# LiDAR_Lite_Interface_HardSwitch.net
KiCad netlist of a schematic drawn in EAGLE
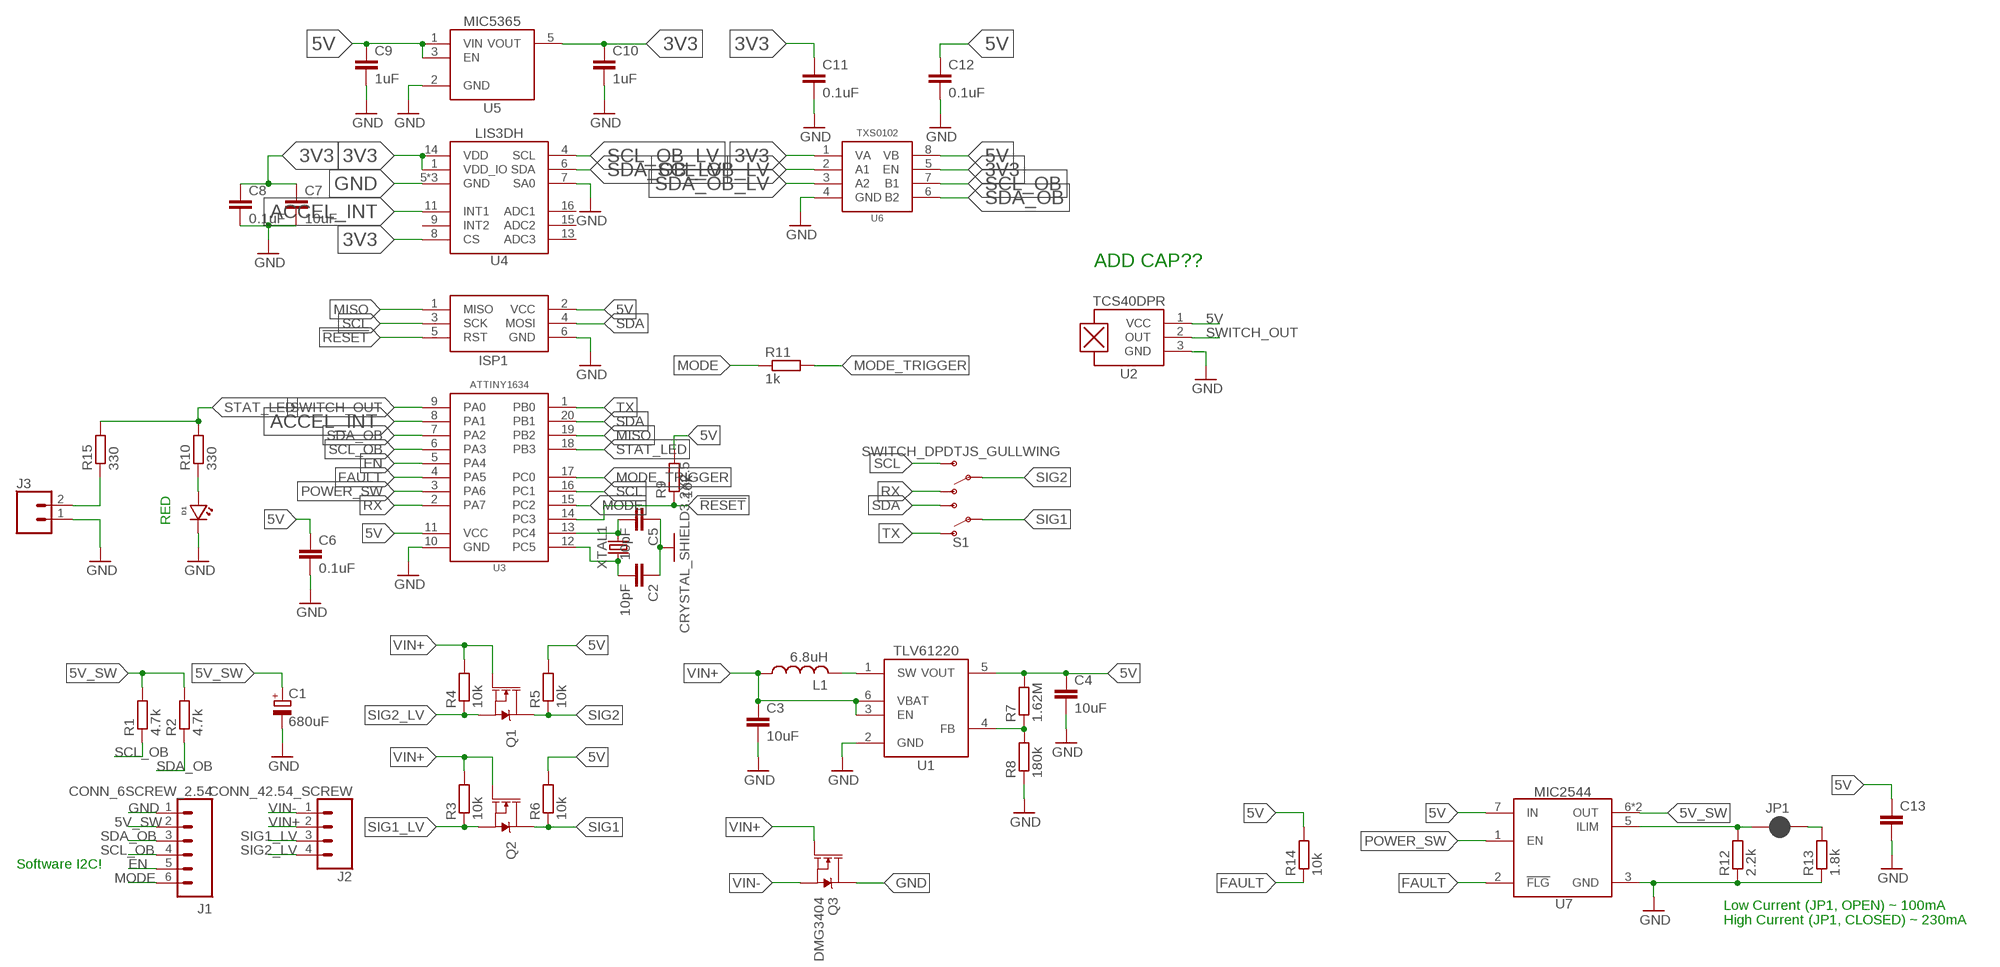
[diagram p0: schematic, sheet 1]

(export (version "E")
  (design (tool "Eeschema 10.0.6"))
  (components
    (comp (ref "C1")
      (value "680uF")
      (footprint "eagle-import:UW-10X10_NICHICON")
      (fields (field (name "MF") "Nichicon") (field (name "MPN") "UWT1C681MNL1GS"))
      (libsource (lib "eagle-import") (part "CPOL-EUUW-10X10"))
    )
    (comp (ref "C2")
      (value "10pF")
      (footprint "eagle-import:C0603")
      (fields (field (name "MF") "Yageo") (field (name "MPN") "CC0603JRNPO9BN100CC0603JRNPO9BN100"))
      (libsource (lib "eagle-import") (part "C-EUC060310PF"))
    )
    (comp (ref "C3")
      (value "10uF")
      (footprint "eagle-import:C0805")
      (fields (field (name "MF") "Murata") (field (name "MPN") "GRM21BR61C106KE15K"))
      (libsource (lib "eagle-import") (part "C-EUC080510UF"))
    )
    (comp (ref "C4")
      (value "10uF")
      (footprint "eagle-import:C0805")
      (fields (field (name "MF") "Murata") (field (name "MPN") "GRM21BR61C106KE15K"))
      (libsource (lib "eagle-import") (part "C-EUC080510UF"))
    )
    (comp (ref "C5")
      (value "10pF")
      (footprint "eagle-import:C0603")
      (fields (field (name "MF") "Yageo") (field (name "MPN") "CC0603JRNPO9BN100CC0603JRNPO9BN100"))
      (libsource (lib "eagle-import") (part "C-EUC060310PF"))
    )
    (comp (ref "C6")
      (value "0.1uF")
      (footprint "eagle-import:C0603")
      (fields (field (name "MF") "Murata") (field (name "MPN") "GCM188R71E104KA57D"))
      (libsource (lib "eagle-import") (part "C-EUC06030.1UF"))
    )
    (comp (ref "C7")
      (value "10uF")
      (footprint "eagle-import:C0805")
      (fields (field (name "MF") "Murata") (field (name "MPN") "GRM21BR61C106KE15K"))
      (libsource (lib "eagle-import") (part "C-EUC080510UF"))
    )
    (comp (ref "C8")
      (value "0.1uF")
      (footprint "eagle-import:C0603")
      (fields (field (name "MF") "Murata") (field (name "MPN") "GCM188R71E104KA57D"))
      (libsource (lib "eagle-import") (part "C-EUC06030.1UF"))
    )
    (comp (ref "C9")
      (value "1uF")
      (footprint "eagle-import:C0603")
      (fields (field (name "MF") "Murata") (field (name "MPN") "GRM188R61C105KA12D"))
      (libsource (lib "eagle-import") (part "C-EUC06031UF"))
    )
    (comp (ref "C10")
      (value "1uF")
      (footprint "eagle-import:C0603")
      (fields (field (name "MF") "Murata") (field (name "MPN") "GRM188R61C105KA12D"))
      (libsource (lib "eagle-import") (part "C-EUC06031UF"))
    )
    (comp (ref "C11")
      (value "0.1uF")
      (footprint "eagle-import:C0402")
      (fields (field (name "MF") "Murata") (field (name "MPN") "GCM155R71C104KA55D"))
      (libsource (lib "eagle-import") (part "C-EUC04020.1UF"))
    )
    (comp (ref "C12")
      (value "0.1uF")
      (footprint "eagle-import:C0402")
      (fields (field (name "MF") "Murata") (field (name "MPN") "GCM155R71C104KA55D"))
      (libsource (lib "eagle-import") (part "C-EUC04020.1UF"))
    )
    (comp (ref "C13")
      (value "C-EU0.1UFC0603")
      (footprint "eagle-import:C0603")
      (fields (field (name "MF") "Murata") (field (name "MPN") "GCM188R71E104KA57D"))
      (libsource (lib "eagle-import") (part "C-EUC06030.1UF"))
    )
    (comp (ref "D1")
      (value "LED0603")
      (footprint "eagle-import:LED_0603")
      (fields
        (field (name "DIGIKEY") "732-4978-1-ND")
        (field (name "MF") "Wurth")
        (field (name "MPN") "150060RS75000")
      )
      (libsource (lib "eagle-import") (part "LED0603"))
    )
    (comp (ref "ISP1")
      (value "AVRISP-6")
      (footprint "eagle-import:AVRISP")
      (libsource (lib "eagle-import") (part "AVRISP-6"))
    )
    (comp (ref "J1")
      (value "CONN_6SCREW_2.54")
      (footprint "eagle-import:1X06_SCREW")
      (fields (field (name "MF") "OnShore") (field (name "MPN") "OSTVN06A150"))
      (libsource (lib "eagle-import") (part "CONN_6SCREW_2.54"))
    )
    (comp (ref "J2")
      (value "CONN_42.54_SCREW")
      (footprint "eagle-import:1X04_SCREW")
      (fields (field (name "MF") "On Shore") (field (name "MPN") "OSTVN04A150"))
      (libsource (lib "eagle-import") (part "CONN_42.54_SCREW"))
    )
    (comp (ref "J3")
      (value "CONN_02")
      (footprint "eagle-import:1X02")
      (libsource (lib "eagle-import") (part "CONN_02"))
    )
    (comp (ref "JP1")
      (value "JUMPER-SMT_2_NC_PASTE_SILK")
      (footprint "eagle-import:SMT-JUMPER_2_NC_PASTE_SILK")
      (libsource (lib "eagle-import") (part "JUMPER-SMT_2_NC_PASTE_SILK"))
    )
    (comp (ref "L1")
      (value "6.8uH")
      (footprint "eagle-import:1008")
      (fields (field (name "MF") "Wurth") (field (name "MPN") "74438323068"))
      (libsource (lib "eagle-import") (part "INDUCTOR1008"))
    )
    (comp (ref "Q1")
      (value "MOSFET-NCH-2N7002P")
      (footprint "eagle-import:SOT23-3")
      (fields (field (name "MF") "Nexperia") (field (name "MPN") "2N7002P,215"))
      (libsource (lib "eagle-import") (part "MOSFET-NCH-2N7002P"))
    )
    (comp (ref "Q2")
      (value "MOSFET-NCH-2N7002P")
      (footprint "eagle-import:SOT23-3")
      (fields (field (name "MF") "Nexperia") (field (name "MPN") "2N7002P,215"))
      (libsource (lib "eagle-import") (part "MOSFET-NCH-2N7002P"))
    )
    (comp (ref "Q3")
      (value "DMG3404")
      (footprint "eagle-import:SOT23-3")
      (fields (field (name "MF") "Diodes Incorporated") (field (name "MPN") "DMG3404L-7"))
      (libsource (lib "eagle-import") (part "MOSFET-NCH-DMG3404L"))
    )
    (comp (ref "R1")
      (value "4.7k")
      (footprint "eagle-import:R0603")
      (fields (field (name "MF") "Yageo") (field (name "MPN") "RC0603FR-074K7L"))
      (libsource (lib "eagle-import") (part "R-EU_R06034.7K"))
    )
    (comp (ref "R2")
      (value "4.7k")
      (footprint "eagle-import:R0603")
      (fields (field (name "MF") "Yageo") (field (name "MPN") "RC0603FR-074K7L"))
      (libsource (lib "eagle-import") (part "R-EU_R06034.7K"))
    )
    (comp (ref "R3")
      (value "10k")
      (footprint "eagle-import:R0603")
      (fields (field (name "MF") "Yageo") (field (name "MPN") "RC0603FR-0710KL"))
      (libsource (lib "eagle-import") (part "R-EU_R060310K"))
    )
    (comp (ref "R4")
      (value "10k")
      (footprint "eagle-import:R0603")
      (fields (field (name "MF") "Yageo") (field (name "MPN") "RC0603FR-0710KL"))
      (libsource (lib "eagle-import") (part "R-EU_R060310K"))
    )
    (comp (ref "R5")
      (value "10k")
      (footprint "eagle-import:R0603")
      (fields (field (name "MF") "Yageo") (field (name "MPN") "RC0603FR-0710KL"))
      (libsource (lib "eagle-import") (part "R-EU_R060310K"))
    )
    (comp (ref "R6")
      (value "10k")
      (footprint "eagle-import:R0603")
      (fields (field (name "MF") "Yageo") (field (name "MPN") "RC0603FR-0710KL"))
      (libsource (lib "eagle-import") (part "R-EU_R060310K"))
    )
    (comp (ref "R7")
      (value "1.62M")
      (footprint "eagle-import:R0603")
      (fields (field (name "MF") "Stackpole") (field (name "MPN") "RMCF0603FT1M62"))
      (libsource (lib "eagle-import") (part "R-EU_R06031.62M"))
    )
    (comp (ref "R8")
      (value "180k")
      (footprint "eagle-import:R0603")
      (fields (field (name "MF") "Panasonic") (field (name "MPN") "ERJ-3EKF1803V"))
      (libsource (lib "eagle-import") (part "R-EU_R0603180K"))
    )
    (comp (ref "R9")
      (value "10k")
      (footprint "eagle-import:R0603")
      (fields (field (name "MF") "Yageo") (field (name "MPN") "RC0603FR-0710KL"))
      (libsource (lib "eagle-import") (part "R-EU_R060310K"))
    )
    (comp (ref "R10")
      (value "330")
      (footprint "eagle-import:R0603")
      (fields (field (name "MF") "Yageo") (field (name "MPN") "RC0603FR-07330RL"))
      (libsource (lib "eagle-import") (part "R-EU_R0603330"))
    )
    (comp (ref "R11")
      (value "1k")
      (footprint "eagle-import:R0603")
      (fields (field (name "MF") "Yageo") (field (name "MPN") "AC0603FR-071KL"))
      (libsource (lib "eagle-import") (part "R-EU_R06031K"))
    )
    (comp (ref "R12")
      (value "2.2k")
      (footprint "eagle-import:R0603")
      (fields (field (name "MF") "Yageo") (field (name "MPN") "RC0603FR-072K2L"))
      (libsource (lib "eagle-import") (part "R-EU_R06032.2K"))
    )
    (comp (ref "R13")
      (value "1.8k")
      (footprint "eagle-import:R0603")
      (fields (field (name "MF") "Yageo") (field (name "MPN") "RC0603FR-071K8L"))
      (libsource (lib "eagle-import") (part "R-EU_R06031.8K"))
    )
    (comp (ref "R14")
      (value "10k")
      (footprint "eagle-import:R0603")
      (fields (field (name "MF") "Yageo") (field (name "MPN") "RC0603FR-0710KL"))
      (libsource (lib "eagle-import") (part "R-EU_R060310K"))
    )
    (comp (ref "R15")
      (value "330")
      (footprint "eagle-import:R0603")
      (fields (field (name "MF") "Yageo") (field (name "MPN") "RC0603FR-07330RL"))
      (libsource (lib "eagle-import") (part "R-EU_R0603330"))
    )
    (comp (ref "S1")
      (value "SWITCH_DPDTJS_GULLWING")
      (footprint "eagle-import:JS202011SCQN")
      (fields (field (name "MF") "C&K") (field (name "MPN") "JS202011SCQN"))
      (libsource (lib "eagle-import") (part "SWITCH_DPDTJS_GULLWING"))
    )
    (comp (ref "U1")
      (value "TLV61220DBV")
      (footprint "eagle-import:DBV_R-PDSO-G6")
      (fields (field (name "MF") "TI") (field (name "MPN") "TLV61220DBVR"))
      (libsource (lib "eagle-import") (part "TLV61220DBV"))
    )
    (comp (ref "U2")
      (value "TCS40DPRSOT23")
      (footprint "eagle-import:SOT23-3")
      (fields
        (field (name "DISP") "TCS40DPR")
        (field (name "MF") "Toshiba")
        (field (name "MPN") "TCS40DPR,LF")
      )
      (libsource (lib "eagle-import") (part "TCS40DPRSOT23"))
    )
    (comp (ref "U3")
      (value "ATTINY1634SOIC")
      (footprint "eagle-import:SO-20DW")
      (fields (field (name "MF") "Atmel") (field (name "MPN") "ATTINY1634-SUR"))
      (libsource (lib "eagle-import") (part "ATTINY1634SOIC"))
    )
    (comp (ref "U4")
      (value "LIS3DHLGA")
      (footprint "eagle-import:LGA-16")
      (fields (field (name "MF") "ST") (field (name "MPN") "LIS3DHTR"))
      (libsource (lib "eagle-import") (part "LIS3DHLGA"))
    )
    (comp (ref "U5")
      (value "MIC53653.3SC70")
      (footprint "eagle-import:DCK_R-PDSO-G5")
      (fields (field (name "MF") "Microchip") (field (name "MPN") "MIC5365-3.3YC5-TR"))
      (libsource (lib "eagle-import") (part "MIC5365SC703.3"))
    )
    (comp (ref "U6")
      (value "TXS0102DQM")
      (footprint "eagle-import:DQM_R-PX2SON-N8")
      (fields (field (name "MF") "TI") (field (name "MPN") "TXS0102DQMR"))
      (libsource (lib "eagle-import") (part "TXS0102DQM"))
    )
    (comp (ref "U7")
      (value "MIC2544MSOP")
      (footprint "eagle-import:MSOP_8")
      (fields (field (name "MF") "Microchip") (field (name "MPN") "MIC2544-1YMM"))
      (libsource (lib "eagle-import") (part "MIC2544MSOP"))
    )
    (comp (ref "XTAL1")
      (value "CRYSTAL_SHIELD3.2X2.5")
      (footprint "eagle-import:CRYSTAL_3.2X2.5_4-SMD")
      (fields (field (name "MF") "Abricon") (field (name "MPN") "ABM8G-12.000MHZ-4Y-T3"))
      (libsource (lib "eagle-import") (part "CRYSTAL_SHIELD3.2X2.5"))
    )
  )
  (nets
    (net (code "1") (name "/~{RESET}") (class "Default")
      (node (ref "ISP1") (pin "5") (pinfunction "RST_5") (pintype "output"))
      (node (ref "R9") (pin "1") (pinfunction "1_1") (pintype "passive"))
      (node (ref "U3") (pin "14") (pinfunction "PC3_14") (pintype "bidirectional"))
    )
    (net (code "2") (name "3V3") (class "Default")
      (node (ref "C10") (pin "1") (pinfunction "1_1") (pintype "passive"))
      (node (ref "C11") (pin "1") (pinfunction "1_1") (pintype "passive"))
      (node (ref "C7") (pin "1") (pinfunction "1_1") (pintype "passive"))
      (node (ref "C8") (pin "1") (pinfunction "1_1") (pintype "passive"))
      (node (ref "U4") (pin "1") (pinfunction "VDD_IO_1") (pintype "bidirectional"))
      (node (ref "U4") (pin "14") (pinfunction "VDD_14") (pintype "bidirectional"))
      (node (ref "U4") (pin "8") (pinfunction "CS_8") (pintype "bidirectional"))
      (node (ref "U5") (pin "5") (pinfunction "VOUT_5") (pintype "power_in"))
      (node (ref "U6") (pin "1") (pinfunction "VA_1") (pintype "power_in"))
      (node (ref "U6") (pin "5") (pinfunction "EN_5") (pintype "input"))
    )
    (net (code "3") (name "5V") (class "Default")
      (node (ref "C12") (pin "1") (pinfunction "1_1") (pintype "passive"))
      (node (ref "C13") (pin "1") (pinfunction "1_1") (pintype "passive"))
      (node (ref "C4") (pin "1") (pinfunction "1_1") (pintype "passive"))
      (node (ref "C6") (pin "1") (pinfunction "1_1") (pintype "passive"))
      (node (ref "C9") (pin "1") (pinfunction "1_1") (pintype "passive"))
      (node (ref "ISP1") (pin "2") (pinfunction "VCC_2") (pintype "power_in"))
      (node (ref "R14") (pin "2") (pinfunction "2_2") (pintype "passive"))
      (node (ref "R5") (pin "2") (pinfunction "2_2") (pintype "passive"))
      (node (ref "R6") (pin "2") (pinfunction "2_2") (pintype "passive"))
      (node (ref "R7") (pin "2") (pinfunction "2_2") (pintype "passive"))
      (node (ref "R9") (pin "2") (pinfunction "2_2") (pintype "passive"))
      (node (ref "U1") (pin "5") (pinfunction "VOUT_5") (pintype "power_in"))
      (node (ref "U2") (pin "1") (pinfunction "VCC_1") (pintype "power_in"))
      (node (ref "U3") (pin "11") (pinfunction "VCC_11") (pintype "power_in"))
      (node (ref "U5") (pin "1") (pinfunction "VIN_1") (pintype "power_in"))
      (node (ref "U5") (pin "3") (pinfunction "EN_3") (pintype "input"))
      (node (ref "U6") (pin "8") (pinfunction "VB_8") (pintype "power_in"))
      (node (ref "U7") (pin "7") (pinfunction "IN_7") (pintype "power_in"))
    )
    (net (code "4") (name "5V_SW") (class "Default")
      (node (ref "C1") (pin "+") (pinfunction "+_+") (pintype "passive"))
      (node (ref "J1") (pin "2") (pinfunction "2_2") (pintype "passive"))
      (node (ref "R1") (pin "2") (pinfunction "2_2") (pintype "passive"))
      (node (ref "R2") (pin "2") (pinfunction "2_2") (pintype "passive"))
      (node (ref "U7") (pin "6") (pinfunction "OUT_6") (pintype "power_in"))
      (node (ref "U7") (pin "8") (pinfunction "OUT_8") (pintype "power_in"))
    )
    (net (code "5") (name "ACCEL_INT") (class "Default")
      (node (ref "U3") (pin "8") (pinfunction "PA1_8") (pintype "bidirectional"))
      (node (ref "U4") (pin "11") (pinfunction "INT1_11") (pintype "bidirectional"))
    )
    (net (code "6") (name "EN") (class "Default")
      (node (ref "J1") (pin "5") (pinfunction "5_5") (pintype "passive"))
      (node (ref "U3") (pin "5") (pinfunction "PA4_5") (pintype "bidirectional"))
    )
    (net (code "7") (name "FAULT") (class "Default")
      (node (ref "R14") (pin "1") (pinfunction "1_1") (pintype "passive"))
      (node (ref "U3") (pin "4") (pinfunction "PA5_4") (pintype "bidirectional"))
      (node (ref "U7") (pin "2") (pinfunction "~{FLG}_2") (pintype "output"))
    )
    (net (code "8") (name "GND") (class "Default")
      (node (ref "C1") (pin "-") (pinfunction "-_-") (pintype "passive"))
      (node (ref "C10") (pin "2") (pinfunction "2_2") (pintype "passive"))
      (node (ref "C11") (pin "2") (pinfunction "2_2") (pintype "passive"))
      (node (ref "C12") (pin "2") (pinfunction "2_2") (pintype "passive"))
      (node (ref "C13") (pin "2") (pinfunction "2_2") (pintype "passive"))
      (node (ref "C2") (pin "1") (pinfunction "1_1") (pintype "passive"))
      (node (ref "C3") (pin "2") (pinfunction "2_2") (pintype "passive"))
      (node (ref "C4") (pin "2") (pinfunction "2_2") (pintype "passive"))
      (node (ref "C5") (pin "1") (pinfunction "1_1") (pintype "passive"))
      (node (ref "C6") (pin "2") (pinfunction "2_2") (pintype "passive"))
      (node (ref "C7") (pin "2") (pinfunction "2_2") (pintype "passive"))
      (node (ref "C8") (pin "2") (pinfunction "2_2") (pintype "passive"))
      (node (ref "C9") (pin "2") (pinfunction "2_2") (pintype "passive"))
      (node (ref "D1") (pin "CATHODE") (pinfunction "CATHODE_CATHODE") (pintype "power_in"))
      (node (ref "ISP1") (pin "6") (pinfunction "GND_6") (pintype "power_in"))
      (node (ref "J1") (pin "1") (pinfunction "1_1") (pintype "passive"))
      (node (ref "J3") (pin "1") (pinfunction "1_1") (pintype "passive"))
      (node (ref "Q3") (pin "3") (pinfunction "D_3") (pintype "bidirectional"))
      (node (ref "R12") (pin "1") (pinfunction "1_1") (pintype "passive"))
      (node (ref "R13") (pin "1") (pinfunction "1_1") (pintype "passive"))
      (node (ref "R8") (pin "1") (pinfunction "1_1") (pintype "passive"))
      (node (ref "U1") (pin "2") (pinfunction "GND_2") (pintype "power_in"))
      (node (ref "U2") (pin "3") (pinfunction "GND_3") (pintype "power_in"))
      (node (ref "U3") (pin "10") (pinfunction "GND_10") (pintype "power_in"))
      (node (ref "U4") (pin "10") (pinfunction "GND_10") (pintype "bidirectional"))
      (node (ref "U4") (pin "12") (pinfunction "GND_12") (pintype "bidirectional"))
      (node (ref "U4") (pin "5") (pinfunction "GND_5") (pintype "bidirectional"))
      (node (ref "U4") (pin "7") (pinfunction "SA0_7") (pintype "bidirectional"))
      (node (ref "U5") (pin "2") (pinfunction "GND_2") (pintype "power_in"))
      (node (ref "U6") (pin "4") (pinfunction "GND_4") (pintype "power_in"))
      (node (ref "U7") (pin "3") (pinfunction "GND_3") (pintype "power_in"))
      (node (ref "XTAL1") (pin "2") (pinfunction "GND_2") (pintype "power_in"))
      (node (ref "XTAL1") (pin "4") (pinfunction "GND_4") (pintype "power_in"))
    )
    (net (code "9") (name "MISO") (class "Default")
      (node (ref "ISP1") (pin "1") (pinfunction "MISO_1") (pintype "input"))
      (node (ref "U3") (pin "19") (pinfunction "PB2_19") (pintype "bidirectional"))
    )
    (net (code "10") (name "MODE") (class "Default")
      (node (ref "J1") (pin "6") (pinfunction "6_6") (pintype "passive"))
      (node (ref "R11") (pin "1") (pinfunction "1_1") (pintype "passive"))
      (node (ref "U3") (pin "15") (pinfunction "PC2_15") (pintype "bidirectional"))
    )
    (net (code "11") (name "MODE_TRIGGER") (class "Default")
      (node (ref "R11") (pin "2") (pinfunction "2_2") (pintype "passive"))
      (node (ref "U3") (pin "17") (pinfunction "PC0_17") (pintype "bidirectional"))
    )
    (net (code "12") (name "Net-(D1-PadANODE)") (class "Default")
      (node (ref "D1") (pin "ANODE") (pinfunction "ANODE_ANODE") (pintype "power_in"))
      (node (ref "R10") (pin "1") (pinfunction "1_1") (pintype "passive"))
    )
    (net (code "13") (name "Net-(J3-Pad2)") (class "Default")
      (node (ref "J3") (pin "2") (pinfunction "2_2") (pintype "passive"))
      (node (ref "R15") (pin "1") (pinfunction "1_1") (pintype "passive"))
    )
    (net (code "14") (name "Net-(JP1-Pad2)") (class "Default")
      (node (ref "JP1") (pin "2") (pinfunction "2_2") (pintype "passive"))
      (node (ref "R13") (pin "2") (pinfunction "2_2") (pintype "passive"))
    )
    (net (code "15") (name "Net-(U1-FB)") (class "Default")
      (node (ref "R7") (pin "1") (pinfunction "1_1") (pintype "passive"))
      (node (ref "R8") (pin "2") (pinfunction "2_2") (pintype "passive"))
      (node (ref "U1") (pin "4") (pinfunction "FB_4") (pintype "input"))
    )
    (net (code "16") (name "Net-(U1-SW)") (class "Default")
      (node (ref "L1") (pin "2") (pinfunction "2_2") (pintype "passive"))
      (node (ref "U1") (pin "1") (pinfunction "SW_1") (pintype "power_in"))
    )
    (net (code "17") (name "Net-(U3-PC4)") (class "Default")
      (node (ref "C5") (pin "2") (pinfunction "2_2") (pintype "passive"))
      (node (ref "U3") (pin "13") (pinfunction "PC4_13") (pintype "bidirectional"))
      (node (ref "XTAL1") (pin "3") (pinfunction "2_3") (pintype "passive"))
    )
    (net (code "18") (name "Net-(U3-PC5)") (class "Default")
      (node (ref "C2") (pin "2") (pinfunction "2_2") (pintype "passive"))
      (node (ref "U3") (pin "12") (pinfunction "PC5_12") (pintype "bidirectional"))
      (node (ref "XTAL1") (pin "1") (pinfunction "1_1") (pintype "passive"))
    )
    (net (code "19") (name "Net-(U7-ILIM)") (class "Default")
      (node (ref "JP1") (pin "1") (pinfunction "1_1") (pintype "passive"))
      (node (ref "R12") (pin "2") (pinfunction "2_2") (pintype "passive"))
      (node (ref "U7") (pin "5") (pinfunction "ILIM_5") (pintype "input"))
    )
    (net (code "20") (name "POWER_SW") (class "Default")
      (node (ref "U3") (pin "3") (pinfunction "PA6_3") (pintype "bidirectional"))
      (node (ref "U7") (pin "1") (pinfunction "EN_1") (pintype "input"))
    )
    (net (code "21") (name "RX") (class "Default")
      (node (ref "S1") (pin "6") (pinfunction "O2_6") (pintype "passive"))
      (node (ref "U3") (pin "2") (pinfunction "PA7_2") (pintype "bidirectional"))
    )
    (net (code "22") (name "SCL") (class "Default")
      (node (ref "ISP1") (pin "3") (pinfunction "SCK_3") (pintype "output"))
      (node (ref "S1") (pin "4") (pinfunction "S2_4") (pintype "passive"))
      (node (ref "U3") (pin "16") (pinfunction "PC1_16") (pintype "bidirectional"))
    )
    (net (code "23") (name "SCL_OB") (class "Default")
      (node (ref "J1") (pin "4") (pinfunction "4_4") (pintype "passive"))
      (node (ref "R1") (pin "1") (pinfunction "1_1") (pintype "passive"))
      (node (ref "U3") (pin "6") (pinfunction "PA3_6") (pintype "bidirectional"))
      (node (ref "U6") (pin "7") (pinfunction "B1_7") (pintype "bidirectional"))
    )
    (net (code "24") (name "SCL_OB_LV") (class "Default")
      (node (ref "U4") (pin "4") (pinfunction "SCL_4") (pintype "bidirectional"))
      (node (ref "U6") (pin "2") (pinfunction "A1_2") (pintype "bidirectional"))
    )
    (net (code "25") (name "SDA") (class "Default")
      (node (ref "ISP1") (pin "4") (pinfunction "MOSI_4") (pintype "output"))
      (node (ref "S1") (pin "3") (pinfunction "S1_3") (pintype "passive"))
      (node (ref "U3") (pin "20") (pinfunction "PB1_20") (pintype "bidirectional"))
    )
    (net (code "26") (name "SDA_OB") (class "Default")
      (node (ref "J1") (pin "3") (pinfunction "3_3") (pintype "passive"))
      (node (ref "R2") (pin "1") (pinfunction "1_1") (pintype "passive"))
      (node (ref "U3") (pin "7") (pinfunction "PA2_7") (pintype "bidirectional"))
      (node (ref "U6") (pin "6") (pinfunction "B2_6") (pintype "bidirectional"))
    )
    (net (code "27") (name "SDA_OB_LV") (class "Default")
      (node (ref "U4") (pin "6") (pinfunction "SDA_6") (pintype "bidirectional"))
      (node (ref "U6") (pin "3") (pinfunction "A2_3") (pintype "bidirectional"))
    )
    (net (code "28") (name "SIG1") (class "Default")
      (node (ref "Q2") (pin "3") (pinfunction "D_3") (pintype "bidirectional"))
      (node (ref "R6") (pin "1") (pinfunction "1_1") (pintype "passive"))
      (node (ref "S1") (pin "2") (pinfunction "P1_2") (pintype "passive"))
    )
    (net (code "29") (name "SIG1_LV") (class "Default")
      (node (ref "J2") (pin "3") (pinfunction "3_3") (pintype "passive"))
      (node (ref "Q2") (pin "2") (pinfunction "S_2") (pintype "bidirectional"))
      (node (ref "R3") (pin "1") (pinfunction "1_1") (pintype "passive"))
    )
    (net (code "30") (name "SIG2") (class "Default")
      (node (ref "Q1") (pin "3") (pinfunction "D_3") (pintype "bidirectional"))
      (node (ref "R5") (pin "1") (pinfunction "1_1") (pintype "passive"))
      (node (ref "S1") (pin "5") (pinfunction "P2_5") (pintype "passive"))
    )
    (net (code "31") (name "SIG2_LV") (class "Default")
      (node (ref "J2") (pin "4") (pinfunction "4_4") (pintype "passive"))
      (node (ref "Q1") (pin "2") (pinfunction "S_2") (pintype "bidirectional"))
      (node (ref "R4") (pin "1") (pinfunction "1_1") (pintype "passive"))
    )
    (net (code "32") (name "STAT_LED") (class "Default")
      (node (ref "R10") (pin "2") (pinfunction "2_2") (pintype "passive"))
      (node (ref "R15") (pin "2") (pinfunction "2_2") (pintype "passive"))
      (node (ref "U3") (pin "18") (pinfunction "PB3_18") (pintype "bidirectional"))
    )
    (net (code "33") (name "SWITCH_OUT") (class "Default")
      (node (ref "U2") (pin "2") (pinfunction "OUT_2") (pintype "output"))
      (node (ref "U3") (pin "9") (pinfunction "PA0_9") (pintype "bidirectional"))
    )
    (net (code "34") (name "TX") (class "Default")
      (node (ref "S1") (pin "1") (pinfunction "O1_1") (pintype "passive"))
      (node (ref "U3") (pin "1") (pinfunction "PB0_1") (pintype "bidirectional"))
    )
    (net (code "35") (name "VIN+") (class "Default")
      (node (ref "C3") (pin "1") (pinfunction "1_1") (pintype "passive"))
      (node (ref "J2") (pin "2") (pinfunction "2_2") (pintype "passive"))
      (node (ref "L1") (pin "1") (pinfunction "1_1") (pintype "passive"))
      (node (ref "Q1") (pin "1") (pinfunction "G_1") (pintype "bidirectional"))
      (node (ref "Q2") (pin "1") (pinfunction "G_1") (pintype "bidirectional"))
      (node (ref "Q3") (pin "1") (pinfunction "G_1") (pintype "bidirectional"))
      (node (ref "R3") (pin "2") (pinfunction "2_2") (pintype "passive"))
      (node (ref "R4") (pin "2") (pinfunction "2_2") (pintype "passive"))
      (node (ref "U1") (pin "3") (pinfunction "EN_3") (pintype "input"))
      (node (ref "U1") (pin "6") (pinfunction "VBAT_6") (pintype "power_in"))
    )
    (net (code "36") (name "VIN-") (class "Default")
      (node (ref "J2") (pin "1") (pinfunction "1_1") (pintype "passive"))
      (node (ref "Q3") (pin "2") (pinfunction "S_2") (pintype "bidirectional"))
    )
    (net (code "37") (name "unconnected-(U4-ADC1-Pad16)") (class "Default")
      (node (ref "U4") (pin "16") (pinfunction "ADC1_16") (pintype "bidirectional"))
    )
    (net (code "38") (name "unconnected-(U4-ADC2-Pad15)") (class "Default")
      (node (ref "U4") (pin "15") (pinfunction "ADC2_15") (pintype "bidirectional"))
    )
    (net (code "39") (name "unconnected-(U4-ADC3-Pad13)") (class "Default")
      (node (ref "U4") (pin "13") (pinfunction "ADC3_13") (pintype "bidirectional"))
    )
    (net (code "40") (name "unconnected-(U4-INT2-Pad9)") (class "Default")
      (node (ref "U4") (pin "9") (pinfunction "INT2_9") (pintype "bidirectional"))
    )
  )
)
